# sensors.net
KiCad netlist of a schematic drawn in Altium Designer
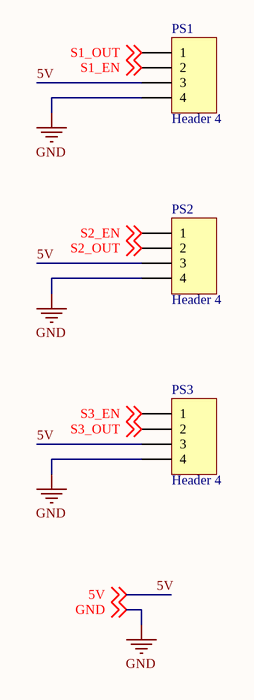
[diagram p0: sensors.SchDoc]

(export (version "E")
  (design (tool "Eeschema 10.0.6"))
  (components
    (comp (ref "PS1")
      (value "Header 4")
      (footprint "HDR1X4")
      (description "Header, 4-Pin")
      (fields (field (name "PUBLISHER") "Altium Limited"))
      (libsource (lib "Miscellaneous Connectors") (part "Header 4"))
    )
    (comp (ref "PS2")
      (value "Header 4")
      (footprint "HDR1X4")
      (description "Header, 4-Pin")
      (fields (field (name "PUBLISHER") "Altium Limited"))
      (libsource (lib "Miscellaneous Connectors") (part "Header 4"))
    )
    (comp (ref "PS3")
      (value "Header 4")
      (footprint "HDR1X4")
      (description "Header, 4-Pin")
      (fields (field (name "PUBLISHER") "Altium Limited"))
      (libsource (lib "Miscellaneous Connectors") (part "Header 4"))
    )
  )
  (nets
    (net (code "1") (name "5V") (class "Default")
      (node (ref "PS1") (pin "3") (pinfunction "3_3") (pintype "passive"))
      (node (ref "PS2") (pin "3") (pinfunction "3_3") (pintype "passive"))
      (node (ref "PS3") (pin "3") (pinfunction "3_3") (pintype "passive"))
    )
    (net (code "2") (name "GND") (class "Default")
      (node (ref "PS1") (pin "4") (pinfunction "4_4") (pintype "passive"))
      (node (ref "PS2") (pin "4") (pinfunction "4_4") (pintype "passive"))
      (node (ref "PS3") (pin "4") (pinfunction "4_4") (pintype "passive"))
    )
    (net (code "3") (name "S1_EN") (class "Default")
      (node (ref "PS1") (pin "2") (pinfunction "2_2") (pintype "passive"))
    )
    (net (code "4") (name "S1_OUT") (class "Default")
      (node (ref "PS1") (pin "1") (pinfunction "1_1") (pintype "passive"))
    )
    (net (code "5") (name "S2_EN") (class "Default")
      (node (ref "PS2") (pin "1") (pinfunction "1_1") (pintype "passive"))
    )
    (net (code "6") (name "S2_OUT") (class "Default")
      (node (ref "PS2") (pin "2") (pinfunction "2_2") (pintype "passive"))
    )
    (net (code "7") (name "S3_EN") (class "Default")
      (node (ref "PS3") (pin "1") (pinfunction "1_1") (pintype "passive"))
    )
    (net (code "8") (name "S3_OUT") (class "Default")
      (node (ref "PS3") (pin "2") (pinfunction "2_2") (pintype "passive"))
    )
  )
)
